# MOTOR_DRIVER_only_top.net
KiCad netlist of a schematic drawn in EAGLE
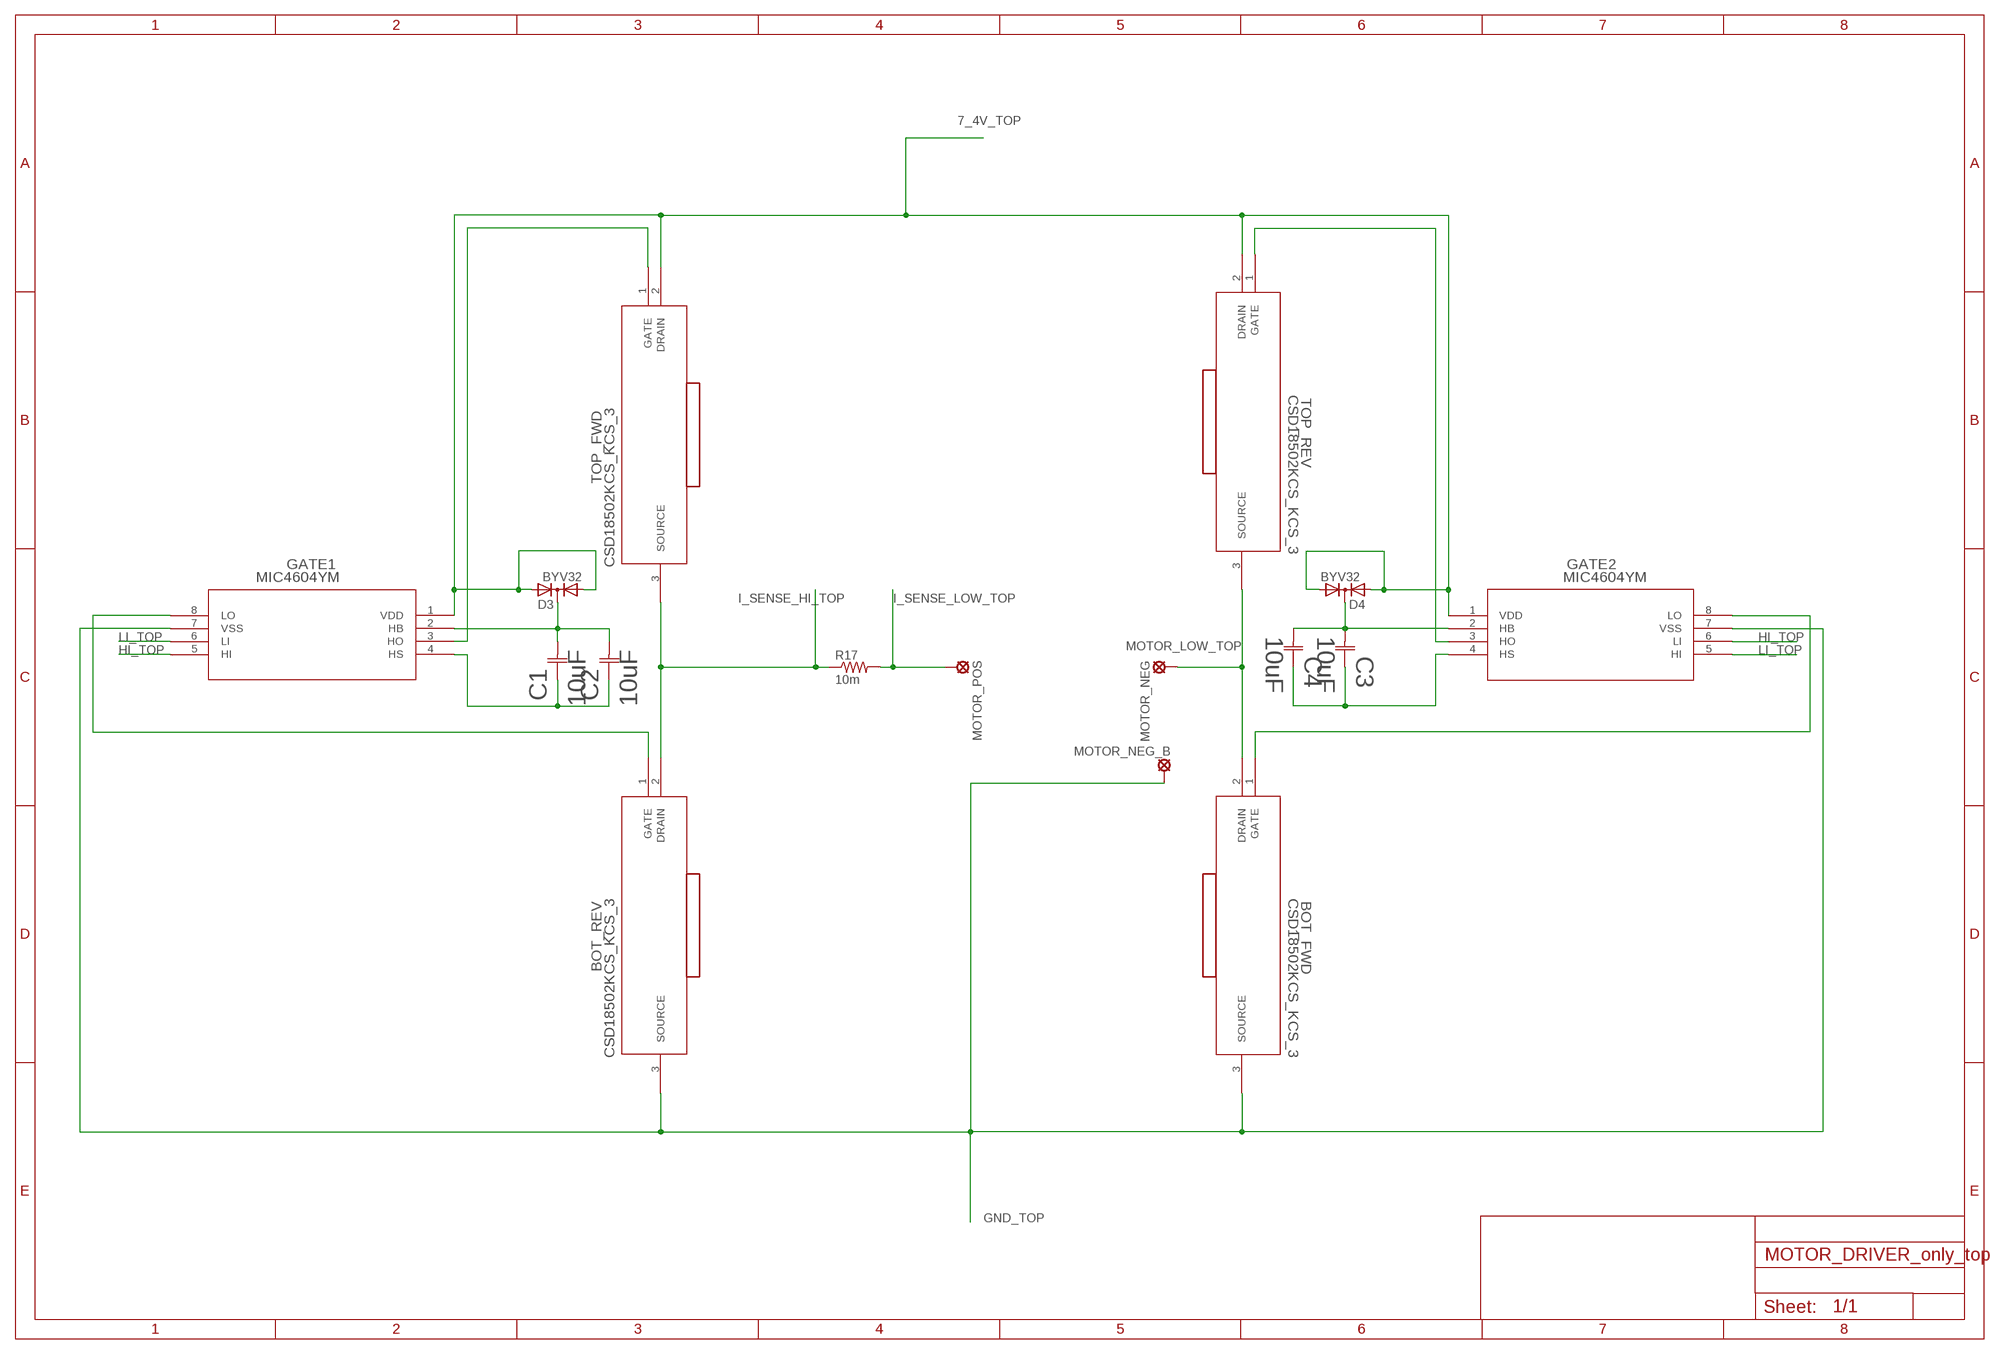
[diagram p0: schematic, sheet 1]

(export (version "E")
  (design (tool "Eeschema 10.0.6"))
  (components
    (comp (ref "BOT_FWD")
      (value "CSD18502KCS_KCS_3")
      (footprint "eagle-import:KCS3")
      (fields
        (field (name "DIGIKEY_PART_NUMBER") "296-35013-ND")
        (field (name "MANUFACTURER") "Texas Instruments")
        (field (name "MANUFACTURER_PART_NUMBER") "CSD18533KCS")
      )
      (libsource (lib "eagle-import") (part "CSD18502KCS_KCS_3"))
    )
    (comp (ref "BOT_REV")
      (value "CSD18502KCS_KCS_3")
      (footprint "eagle-import:KCS3")
      (fields
        (field (name "DIGIKEY_PART_NUMBER") "296-35013-ND")
        (field (name "MANUFACTURER") "Texas Instruments")
        (field (name "MANUFACTURER_PART_NUMBER") "CSD18533KCS")
      )
      (libsource (lib "eagle-import") (part "CSD18502KCS_KCS_3"))
    )
    (comp (ref "C1")
      (value "10uF")
      (footprint "eagle-import:CAP_EEE_B")
      (fields (field (name "MANUFACTURER_PART_NUMBER") "EEE1VA100WR"))
      (libsource (lib "eagle-import") (part "EEE1VA100WR"))
    )
    (comp (ref "C2")
      (value "10uF")
      (footprint "eagle-import:CAP_EEE_B")
      (fields (field (name "MANUFACTURER_PART_NUMBER") "EEE1VA100WR"))
      (libsource (lib "eagle-import") (part "EEE1VA100WR"))
    )
    (comp (ref "C3")
      (value "10uF")
      (footprint "eagle-import:CAP_EEE_B")
      (fields (field (name "MANUFACTURER_PART_NUMBER") "EEE1VA100WR"))
      (libsource (lib "eagle-import") (part "EEE1VA100WR"))
    )
    (comp (ref "C4")
      (value "10uF")
      (footprint "eagle-import:CAP_EEE_B")
      (fields (field (name "MANUFACTURER_PART_NUMBER") "EEE1VA100WR"))
      (libsource (lib "eagle-import") (part "EEE1VA100WR"))
    )
    (comp (ref "D3")
      (value "BYV32")
      (footprint "eagle-import:TO220ABS")
      (libsource (lib "eagle-import") (part "BYV32"))
    )
    (comp (ref "D4")
      (value "BYV32")
      (footprint "eagle-import:TO220ABS")
      (libsource (lib "eagle-import") (part "BYV32"))
    )
    (comp (ref "GATE1")
      (value "MIC4604YM")
      (footprint "eagle-import:SOIC-8_M")
      (fields
        (field (name "DIGIKEY_PART_NUMBER") "576-4395-1-ND")
        (field (name "MANUFACTURER") "Microchip")
        (field (name "MANUFACTURER_PART_NUMBER") "MIC4604YM-T5")
      )
      (libsource (lib "eagle-import") (part "MIC4604YM"))
    )
    (comp (ref "GATE2")
      (value "MIC4604YM")
      (footprint "eagle-import:SOIC-8_M")
      (fields
        (field (name "DIGIKEY_PART_NUMBER") "576-4395-1-ND")
        (field (name "MANUFACTURER") "Microchip")
        (field (name "MANUFACTURER_PART_NUMBER") "MIC4604YM-T5")
      )
      (libsource (lib "eagle-import") (part "MIC4604YM"))
    )
    (comp (ref "MOTOR_NEG")
      (value "SE14")
      (footprint "eagle-import:SE14")
      (libsource (lib "eagle-import") (part "SE14"))
    )
    (comp (ref "MOTOR_NEG_B")
      (value "SE14")
      (footprint "eagle-import:SE14")
      (libsource (lib "eagle-import") (part "SE14"))
    )
    (comp (ref "MOTOR_POS")
      (value "SE14")
      (footprint "eagle-import:SE14")
      (libsource (lib "eagle-import") (part "SE14"))
    )
    (comp (ref "R17")
      (value "10m")
      (footprint "eagle-import:R2512")
      (libsource (lib "eagle-import") (part "R-US_R2512"))
    )
    (comp (ref "TOP_FWD")
      (value "CSD18502KCS_KCS_3")
      (footprint "eagle-import:KCS3")
      (fields
        (field (name "DIGIKEY_PART_NUMBER") "296-35013-ND")
        (field (name "MANUFACTURER") "Texas Instruments")
        (field (name "MANUFACTURER_PART_NUMBER") "CSD18533KCS")
      )
      (libsource (lib "eagle-import") (part "CSD18502KCS_KCS_3"))
    )
    (comp (ref "TOP_REV")
      (value "CSD18502KCS_KCS_3")
      (footprint "eagle-import:KCS3")
      (fields
        (field (name "DIGIKEY_PART_NUMBER") "296-35013-ND")
        (field (name "MANUFACTURER") "Texas Instruments")
        (field (name "MANUFACTURER_PART_NUMBER") "CSD18533KCS")
      )
      (libsource (lib "eagle-import") (part "CSD18502KCS_KCS_3"))
    )
    (comp (ref "U$2")
      (value "HEATSINK")
      (footprint "eagle-import:HEATSINK")
      (fields
        (field (name "DIGIKEY_PART_NUMBER") "HS112-ND")
        (field (name "MANUFACTURER") "Aavid Thermalloy")
        (field (name "MANUFACTURER_PART_NUMBER") "507002B00000G")
      )
      (libsource (lib "eagle-import") (part "HEATSINK"))
    )
    (comp (ref "U$4")
      (value "HEATSINK")
      (footprint "eagle-import:HEATSINK")
      (fields
        (field (name "DIGIKEY_PART_NUMBER") "HS112-ND")
        (field (name "MANUFACTURER") "Aavid Thermalloy")
        (field (name "MANUFACTURER_PART_NUMBER") "507002B00000G")
      )
      (libsource (lib "eagle-import") (part "HEATSINK"))
    )
    (comp (ref "U$5")
      (value "HEATSINK")
      (footprint "eagle-import:HEATSINK")
      (fields
        (field (name "DIGIKEY_PART_NUMBER") "HS112-ND")
        (field (name "MANUFACTURER") "Aavid Thermalloy")
        (field (name "MANUFACTURER_PART_NUMBER") "507002B00000G")
      )
      (libsource (lib "eagle-import") (part "HEATSINK"))
    )
    (comp (ref "U$6")
      (value "HEATSINK")
      (footprint "eagle-import:HEATSINK")
      (fields
        (field (name "DIGIKEY_PART_NUMBER") "HS112-ND")
        (field (name "MANUFACTURER") "Aavid Thermalloy")
        (field (name "MANUFACTURER_PART_NUMBER") "507002B00000G")
      )
      (libsource (lib "eagle-import") (part "HEATSINK"))
    )
  )
  (nets
    (net (code "1") (name "/7_4V_TOP") (class "Default")
      (node (ref "D3") (pin "A1") (pinfunction "A1_A1") (pintype "passive"))
      (node (ref "D3") (pin "A2") (pinfunction "A2_A2") (pintype "passive"))
      (node (ref "D4") (pin "A1") (pinfunction "A1_A1") (pintype "passive"))
      (node (ref "D4") (pin "A2") (pinfunction "A2_A2") (pintype "passive"))
      (node (ref "GATE1") (pin "1") (pinfunction "VDD_1") (pintype "power_in"))
      (node (ref "GATE2") (pin "1") (pinfunction "VDD_1") (pintype "power_in"))
      (node (ref "TOP_FWD") (pin "2") (pinfunction "DRAIN_2") (pintype "passive"))
      (node (ref "TOP_REV") (pin "2") (pinfunction "DRAIN_2") (pintype "passive"))
    )
    (net (code "2") (name "/GND_TOP") (class "Default")
      (node (ref "BOT_FWD") (pin "3") (pinfunction "SOURCE_3") (pintype "passive"))
      (node (ref "BOT_REV") (pin "3") (pinfunction "SOURCE_3") (pintype "passive"))
      (node (ref "GATE1") (pin "7") (pinfunction "VSS_7") (pintype "power_in"))
      (node (ref "GATE2") (pin "7") (pinfunction "VSS_7") (pintype "power_in"))
      (node (ref "MOTOR_NEG_B") (pin "MP") (pinfunction "MP_MP") (pintype "passive"))
    )
    (net (code "3") (name "/HI_TOP") (class "Default")
      (node (ref "GATE1") (pin "5") (pinfunction "HI_5") (pintype "input"))
      (node (ref "GATE2") (pin "6") (pinfunction "LI_6") (pintype "input"))
    )
    (net (code "4") (name "/I_SENSE_HI_TOP") (class "Default")
      (node (ref "BOT_REV") (pin "2") (pinfunction "DRAIN_2") (pintype "passive"))
      (node (ref "R17") (pin "1") (pinfunction "1_1") (pintype "passive"))
      (node (ref "TOP_FWD") (pin "3") (pinfunction "SOURCE_3") (pintype "passive"))
    )
    (net (code "5") (name "/I_SENSE_LOW_TOP") (class "Default")
      (node (ref "MOTOR_POS") (pin "MP") (pinfunction "MP_MP") (pintype "passive"))
      (node (ref "R17") (pin "2") (pinfunction "2_2") (pintype "passive"))
    )
    (net (code "6") (name "/LI_TOP") (class "Default")
      (node (ref "GATE1") (pin "6") (pinfunction "LI_6") (pintype "input"))
      (node (ref "GATE2") (pin "5") (pinfunction "HI_5") (pintype "input"))
    )
    (net (code "7") (name "/MOTOR_LOW_TOP") (class "Default")
      (node (ref "BOT_FWD") (pin "2") (pinfunction "DRAIN_2") (pintype "passive"))
      (node (ref "MOTOR_NEG") (pin "MP") (pinfunction "MP_MP") (pintype "passive"))
      (node (ref "TOP_REV") (pin "3") (pinfunction "SOURCE_3") (pintype "passive"))
    )
    (net (code "8") (name "Net-(BOT_FWD-GATE)") (class "Default")
      (node (ref "BOT_FWD") (pin "1") (pinfunction "GATE_1") (pintype "passive"))
      (node (ref "GATE2") (pin "8") (pinfunction "LO_8") (pintype "output"))
    )
    (net (code "9") (name "Net-(BOT_REV-GATE)") (class "Default")
      (node (ref "BOT_REV") (pin "1") (pinfunction "GATE_1") (pintype "passive"))
      (node (ref "GATE1") (pin "8") (pinfunction "LO_8") (pintype "output"))
    )
    (net (code "10") (name "Net-(GATE1-HB)") (class "Default")
      (node (ref "C1") (pin "2") (pinfunction "2_2") (pintype "passive"))
      (node (ref "C2") (pin "2") (pinfunction "2_2") (pintype "passive"))
      (node (ref "D3") (pin "C") (pinfunction "C_C") (pintype "passive"))
      (node (ref "GATE1") (pin "2") (pinfunction "HB_2") (pintype "passive"))
    )
    (net (code "11") (name "Net-(GATE1-HO)") (class "Default")
      (node (ref "GATE1") (pin "3") (pinfunction "HO_3") (pintype "output"))
      (node (ref "TOP_FWD") (pin "1") (pinfunction "GATE_1") (pintype "passive"))
    )
    (net (code "12") (name "Net-(GATE1-HS)") (class "Default")
      (node (ref "C1") (pin "1") (pinfunction "1_1") (pintype "passive"))
      (node (ref "C2") (pin "1") (pinfunction "1_1") (pintype "passive"))
      (node (ref "GATE1") (pin "4") (pinfunction "HS_4") (pintype "passive"))
    )
    (net (code "13") (name "Net-(GATE2-HB)") (class "Default")
      (node (ref "C3") (pin "2") (pinfunction "2_2") (pintype "passive"))
      (node (ref "C4") (pin "2") (pinfunction "2_2") (pintype "passive"))
      (node (ref "D4") (pin "C") (pinfunction "C_C") (pintype "passive"))
      (node (ref "GATE2") (pin "2") (pinfunction "HB_2") (pintype "passive"))
    )
    (net (code "14") (name "Net-(GATE2-HO)") (class "Default")
      (node (ref "GATE2") (pin "3") (pinfunction "HO_3") (pintype "output"))
      (node (ref "TOP_REV") (pin "1") (pinfunction "GATE_1") (pintype "passive"))
    )
    (net (code "15") (name "Net-(GATE2-HS)") (class "Default")
      (node (ref "C3") (pin "1") (pinfunction "1_1") (pintype "passive"))
      (node (ref "C4") (pin "1") (pinfunction "1_1") (pintype "passive"))
      (node (ref "GATE2") (pin "4") (pinfunction "HS_4") (pintype "passive"))
    )
  )
)
